# ModMoPSS_-_IR_sender.net
KiCad netlist of a schematic drawn in EAGLE
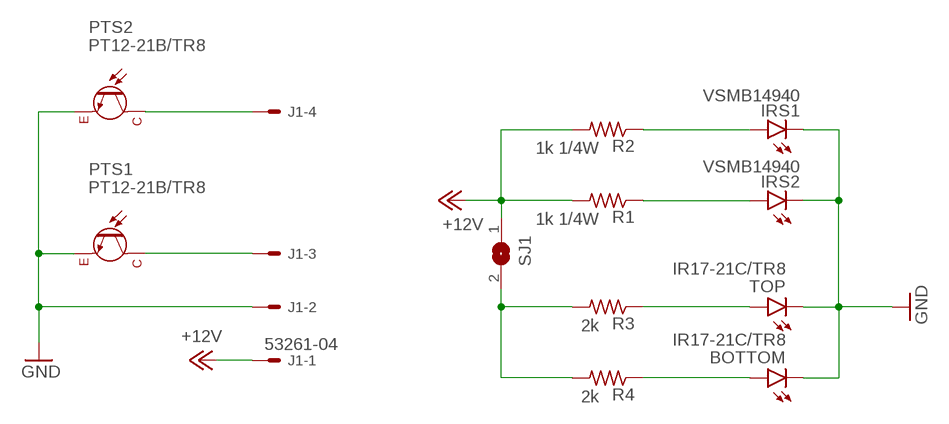
[diagram p0: schematic, sheet 1]

(export (version "E")
  (design (tool "Eeschema 10.0.6"))
  (components
    (comp (ref "BOTTOM")
      (value "IR17-21C/TR8")
      (footprint "eagle-import:CHIP-LED0805")
      (libsource (lib "eagle-import") (part "LEDCHIP-LED0805"))
    )
    (comp (ref "IRS1")
      (value "VSMB14940")
      (footprint "eagle-import:VSMB14940")
      (libsource (lib "eagle-import") (part "VSMB14940"))
    )
    (comp (ref "IRS2")
      (value "VSMB14940")
      (footprint "eagle-import:VSMB14940")
      (libsource (lib "eagle-import") (part "VSMB14940"))
    )
    (comp (ref "J1")
      (value "53261-04")
      (footprint "eagle-import:53261-04")
      (fields (field (name "MF") "MOLEX"))
      (libsource (lib "eagle-import") (part "53?-04261"))
    )
    (comp (ref "PTS1")
      (value "PT12-21B/TR8")
      (footprint "eagle-import:PT12-21B_TR8")
      (libsource (lib "eagle-import") (part "PT12-21B/TR8"))
    )
    (comp (ref "PTS2")
      (value "PT12-21B/TR8")
      (footprint "eagle-import:PT12-21B_TR8")
      (libsource (lib "eagle-import") (part "PT12-21B/TR8"))
    )
    (comp (ref "R1")
      (value "1k 1/4W")
      (footprint "eagle-import:R0805")
      (libsource (lib "eagle-import") (part "R-US_R0805"))
    )
    (comp (ref "R2")
      (value "1k 1/4W")
      (footprint "eagle-import:R0805")
      (libsource (lib "eagle-import") (part "R-US_R0805"))
    )
    (comp (ref "R3")
      (value "2k")
      (footprint "eagle-import:R0805")
      (libsource (lib "eagle-import") (part "R-US_R0805"))
    )
    (comp (ref "R4")
      (value "2k")
      (footprint "eagle-import:R0805")
      (libsource (lib "eagle-import") (part "R-US_R0805"))
    )
    (comp (ref "SJ1") (value "SJ") (footprint "eagle-import:SJ") (libsource (lib "eagle-import") (part "SJ")))
    (comp (ref "TOP")
      (value "IR17-21C/TR8")
      (footprint "eagle-import:CHIP-LED0805")
      (libsource (lib "eagle-import") (part "LEDCHIP-LED0805"))
    )
  )
  (nets
    (net (code "1") (name "+12V") (class "Default")
      (node (ref "J1") (pin "1") (pinfunction "S_1") (pintype "passive"))
      (node (ref "R1") (pin "2") (pinfunction "2_2") (pintype "passive"))
      (node (ref "R2") (pin "2") (pinfunction "2_2") (pintype "passive"))
      (node (ref "SJ1") (pin "1") (pinfunction "1_1") (pintype "passive"))
    )
    (net (code "2") (name "GND") (class "Default")
      (node (ref "BOTTOM") (pin "C") (pinfunction "C_C") (pintype "passive"))
      (node (ref "IRS1") (pin "P$2") (pinfunction "C_P$2") (pintype "passive"))
      (node (ref "IRS2") (pin "P$2") (pinfunction "C_P$2") (pintype "passive"))
      (node (ref "J1") (pin "2") (pinfunction "S_2") (pintype "passive"))
      (node (ref "PTS1") (pin "P$2") (pinfunction "E_P$2") (pintype "passive"))
      (node (ref "PTS2") (pin "P$2") (pinfunction "E_P$2") (pintype "passive"))
      (node (ref "TOP") (pin "C") (pinfunction "C_C") (pintype "passive"))
    )
    (net (code "3") (name "Net-(BOTTOM-PadA)") (class "Default")
      (node (ref "BOTTOM") (pin "A") (pinfunction "A_A") (pintype "passive"))
      (node (ref "R4") (pin "1") (pinfunction "1_1") (pintype "passive"))
    )
    (net (code "4") (name "Net-(IRS1-A)") (class "Default")
      (node (ref "IRS1") (pin "P$1") (pinfunction "A_P$1") (pintype "passive"))
      (node (ref "R2") (pin "1") (pinfunction "1_1") (pintype "passive"))
    )
    (net (code "5") (name "Net-(IRS2-A)") (class "Default")
      (node (ref "IRS2") (pin "P$1") (pinfunction "A_P$1") (pintype "passive"))
      (node (ref "R1") (pin "1") (pinfunction "1_1") (pintype "passive"))
    )
    (net (code "6") (name "Net-(J1C-S)") (class "Default")
      (node (ref "J1") (pin "3") (pinfunction "S_3") (pintype "passive"))
      (node (ref "PTS1") (pin "P$1") (pinfunction "C_P$1") (pintype "passive"))
    )
    (net (code "7") (name "Net-(J1D-S)") (class "Default")
      (node (ref "J1") (pin "4") (pinfunction "S_4") (pintype "passive"))
      (node (ref "PTS2") (pin "P$1") (pinfunction "C_P$1") (pintype "passive"))
    )
    (net (code "8") (name "Net-(R3-Pad1)") (class "Default")
      (node (ref "R3") (pin "1") (pinfunction "1_1") (pintype "passive"))
      (node (ref "TOP") (pin "A") (pinfunction "A_A") (pintype "passive"))
    )
    (net (code "9") (name "Net-(R3-Pad2)") (class "Default")
      (node (ref "R3") (pin "2") (pinfunction "2_2") (pintype "passive"))
      (node (ref "R4") (pin "2") (pinfunction "2_2") (pintype "passive"))
      (node (ref "SJ1") (pin "2") (pinfunction "2_2") (pintype "passive"))
    )
  )
)
